# OVSR.net
KiCad netlist of a schematic drawn in Altium Designer
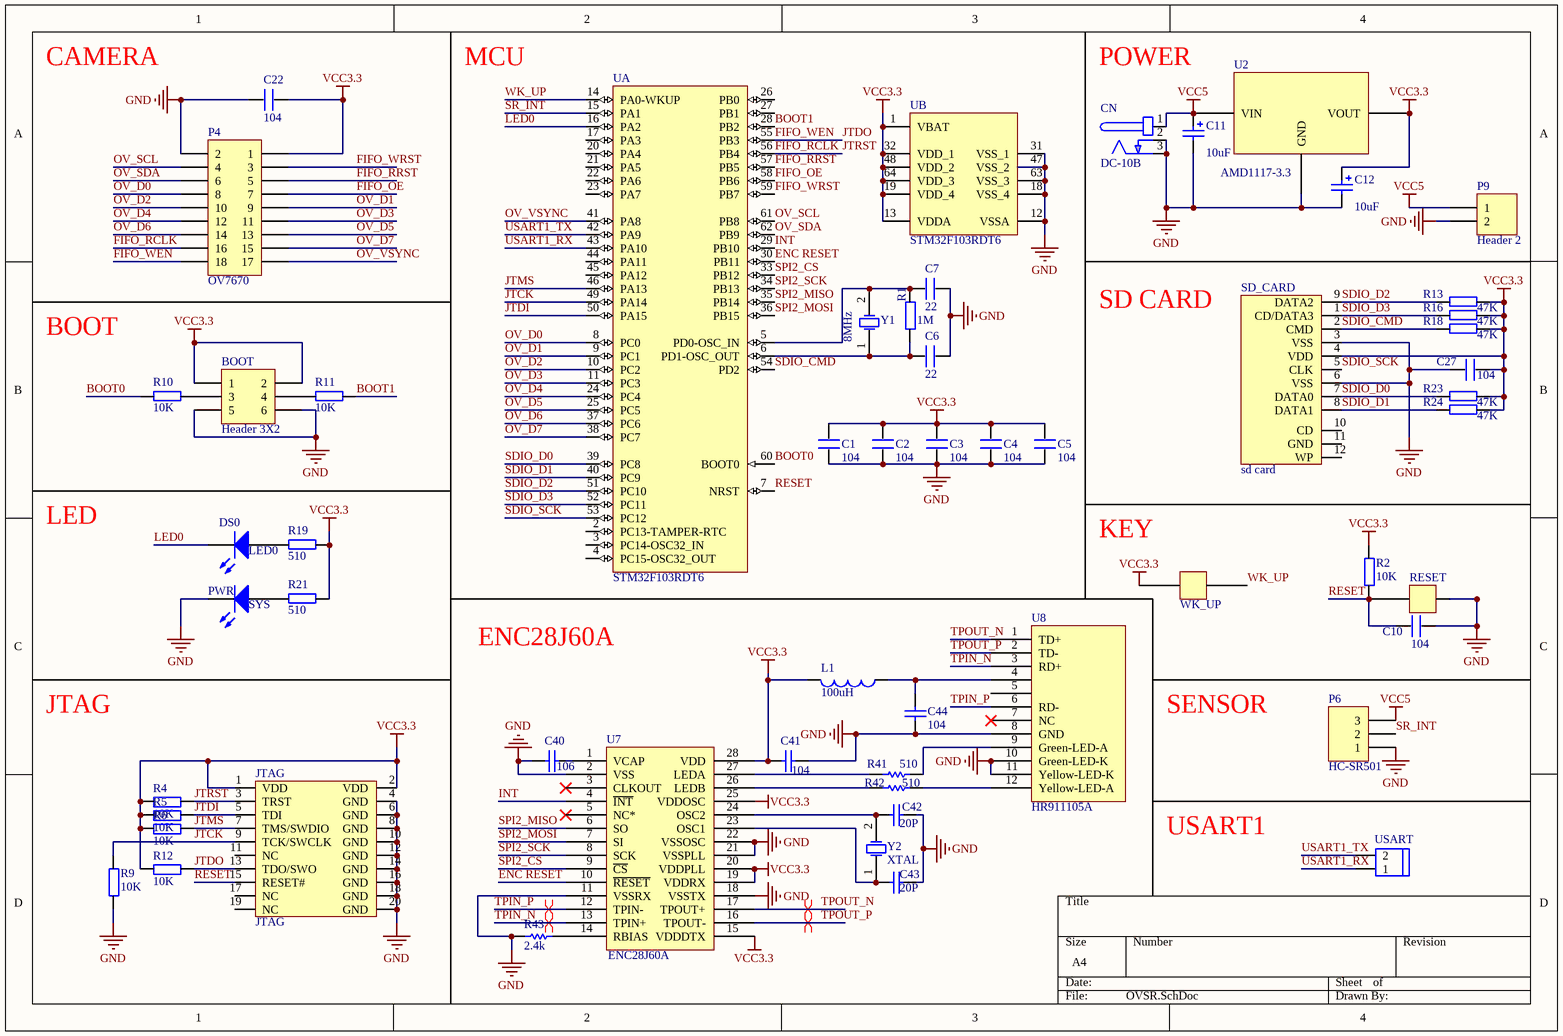
[diagram p0: OVSR.SchDoc]

(export (version "E")
  (design (tool "Eeschema 10.0.6"))
  (components
    (comp (ref "BOOT")
      (value "Header 3X2")
      (footprint "HDR2X3")
      (description "Header, 3-Pin, Dual row")
      (fields (field (name "PUBLISHER") "Altium Limited"))
      (libsource (lib "EliteSTM32封装库") (part "Header 3X2"))
    )
    (comp (ref "C1") (value "104") (footprint "CC1608-0603") (libsource (lib "EliteSTM32封装库") (part "C")))
    (comp (ref "C2") (value "104") (footprint "CC1608-0603") (libsource (lib "EliteSTM32封装库") (part "C")))
    (comp (ref "C3") (value "104") (footprint "CC1608-0603") (libsource (lib "EliteSTM32封装库") (part "C")))
    (comp (ref "C4") (value "104") (footprint "CC1608-0603") (libsource (lib "EliteSTM32封装库") (part "C")))
    (comp (ref "C5") (value "104") (footprint "CC1608-0603") (libsource (lib "EliteSTM32封装库") (part "C")))
    (comp (ref "C6") (value "22") (footprint "CC1608-0603") (libsource (lib "EliteSTM32封装库") (part "C_1")))
    (comp (ref "C7") (value "22") (footprint "CC1608-0603") (libsource (lib "EliteSTM32封装库") (part "C_1")))
    (comp (ref "C10") (value "104") (footprint "CC1608-0603") (libsource (lib "EliteSTM32封装库") (part "C")))
    (comp (ref "C11")
      (value "10uF")
      (footprint "CC1608-0603")
      (description "Polarized Capacitor (Axial)")
      (fields (field (name "Comment") "Cap Pol2") (field (name "PUBLISHER") "Altium Limited"))
      (libsource (lib "Miscellaneous Devices") (part "Cap Pol2"))
    )
    (comp (ref "C12")
      (value "10uF")
      (footprint "CC1608-0603")
      (description "Polarized Capacitor (Axial)")
      (fields (field (name "Comment") "Cap Pol2") (field (name "PUBLISHER") "Altium Limited"))
      (libsource (lib "Miscellaneous Devices") (part "Cap Pol2"))
    )
    (comp (ref "C22") (value "104") (footprint "CC1608-0603") (libsource (lib "EliteSTM32封装库") (part "C")))
    (comp (ref "C27") (value "104") (footprint "CC1608-0603") (libsource (lib "EliteSTM32封装库") (part "C")))
    (comp (ref "C40")
      (value "106")
      (footprint "Cr1608-0603")
      (description "Capacitor")
      (fields (field (name "Comment") "Cap") (field (name "PUBLISHER") "Altium Limited"))
      (libsource (lib "Miscellaneous Devices") (part "Cap"))
    )
    (comp (ref "C41")
      (value "104")
      (footprint "Cr1608-0603")
      (description "Capacitor")
      (fields (field (name "Comment") "Cap") (field (name "PUBLISHER") "Altium Limited"))
      (libsource (lib "Miscellaneous Devices") (part "Cap"))
    )
    (comp (ref "C42")
      (value "20P")
      (footprint "Cr1608-0603")
      (description "Capacitor")
      (fields (field (name "Comment") "Cap") (field (name "PUBLISHER") "Altium Limited"))
      (libsource (lib "Miscellaneous Devices") (part "Cap"))
    )
    (comp (ref "C43")
      (value "20P")
      (footprint "Cr1608-0603")
      (description "Capacitor")
      (fields (field (name "Comment") "Cap") (field (name "PUBLISHER") "Altium Limited"))
      (libsource (lib "Miscellaneous Devices") (part "Cap"))
    )
    (comp (ref "C44")
      (value "104")
      (footprint "Cr1608-0603")
      (description "Capacitor")
      (fields (field (name "Comment") "Cap") (field (name "PUBLISHER") "Altium Limited"))
      (libsource (lib "Miscellaneous Devices") (part "Cap"))
    )
    (comp (ref "CN")
      (value "DC-10B")
      (footprint "DC10B")
      (libsource (lib "STM32F207开发板（基本型）V1.0") (part "PJ202A"))
    )
    (comp (ref "DS0")
      (value "LED0")
      (footprint "WSN3:Cr2012-0805")
      (description "Typical RED, GREEN, YELLOW, AMBER GaAs LED")
      (fields (field (name "PUBLISHER") "Altium Limited"))
      (libsource (lib "EliteSTM32封装库") (part "LED2"))
    )
    (comp (ref "JTAG") (value "JTAG") (footprint "JTAG_20") (libsource (lib "EliteSTM32封装库") (part "JTAG")))
    (comp (ref "L1")
      (value "100uH")
      (footprint "1206")
      (description "Inductor")
      (fields (field (name "PUBLISHER") "Altium Limited"))
      (libsource (lib "Miscellaneous Devices") (part "Inductor"))
    )
    (comp (ref "P4")
      (value "OV7670")
      (footprint "HDR2X9")
      (description "Header, 9-Pin, Dual row")
      (fields (field (name "PUBLISHER") "Altium Limited"))
      (libsource (lib "EliteSTM32封装库") (part "Header 9X2"))
    )
    (comp (ref "P6")
      (value "HC-SR501")
      (footprint "5.08-3")
      (description "Header, 3-Pin")
      (fields (field (name "PUBLISHER") "Altium Limited"))
      (libsource (lib "WSN") (part "Header 3"))
    )
    (comp (ref "P9")
      (value "Header 2")
      (footprint "5.08-2")
      (description "Header, 2-Pin")
      (fields (field (name "PUBLISHER") "Altium Limited"))
      (libsource (lib "WSN") (part "Header 2"))
    )
    (comp (ref "PWR")
      (value "SYS")
      (footprint "WSN3:Cr2012-0805")
      (description "Typical RED, GREEN, YELLOW, AMBER GaAs LED")
      (fields (field (name "PUBLISHER") "Altium Limited"))
      (libsource (lib "EliteSTM32封装库") (part "LED2"))
    )
    (comp (ref "R1") (value "1M") (footprint "CR1608-0603") (libsource (lib "EliteSTM32封装库") (part "R")))
    (comp (ref "R2") (value "10K") (footprint "CR1608-0603") (libsource (lib "EliteSTM32封装库") (part "R")))
    (comp (ref "R4") (value "10K") (footprint "CR1608-0603") (libsource (lib "EliteSTM32封装库") (part "R")))
    (comp (ref "R5") (value "10K") (footprint "CR1608-0603") (libsource (lib "EliteSTM32封装库") (part "R")))
    (comp (ref "R6") (value "10K") (footprint "CR1608-0603") (libsource (lib "EliteSTM32封装库") (part "R")))
    (comp (ref "R9") (value "10K") (footprint "CR1608-0603") (libsource (lib "EliteSTM32封装库") (part "R")))
    (comp (ref "R10") (value "10K") (footprint "CR1608-0603") (libsource (lib "EliteSTM32封装库") (part "R")))
    (comp (ref "R11") (value "10K") (footprint "CR1608-0603") (libsource (lib "EliteSTM32封装库") (part "R")))
    (comp (ref "R12") (value "10K") (footprint "CR1608-0603") (libsource (lib "EliteSTM32封装库") (part "R")))
    (comp (ref "R13") (value "47K") (footprint "CR1608-0603") (libsource (lib "EliteSTM32封装库") (part "R")))
    (comp (ref "R16") (value "47K") (footprint "CR1608-0603") (libsource (lib "EliteSTM32封装库") (part "R")))
    (comp (ref "R18") (value "47K") (footprint "CR1608-0603") (libsource (lib "EliteSTM32封装库") (part "R")))
    (comp (ref "R19") (value "510") (footprint "CR1608-0603") (libsource (lib "EliteSTM32封装库") (part "R")))
    (comp (ref "R21") (value "510") (footprint "CR1608-0603") (libsource (lib "EliteSTM32封装库") (part "R")))
    (comp (ref "R23") (value "47K") (footprint "CR1608-0603") (libsource (lib "EliteSTM32封装库") (part "R")))
    (comp (ref "R24") (value "47K") (footprint "CR1608-0603") (libsource (lib "EliteSTM32封装库") (part "R")))
    (comp (ref "R41")
      (value "510")
      (footprint "Cr1608-0603")
      (description "Resistor")
      (fields (field (name "Comment") "Res1") (field (name "PUBLISHER") "Altium Limited"))
      (libsource (lib "Miscellaneous Devices") (part "Res1"))
    )
    (comp (ref "R42")
      (value "510")
      (footprint "Cr1608-0603")
      (description "Resistor")
      (fields (field (name "Comment") "Res1") (field (name "PUBLISHER") "Altium Limited"))
      (libsource (lib "Miscellaneous Devices") (part "Res1"))
    )
    (comp (ref "R43")
      (value "2.4k")
      (footprint "Cr1608-0603")
      (description "Resistor")
      (fields (field (name "Comment") "Res1") (field (name "PUBLISHER") "Altium Limited"))
      (libsource (lib "Miscellaneous Devices") (part "Res1"))
    )
    (comp (ref "RESET") (value "SW") (footprint "RST_SW") (libsource (lib "MCU") (part "SW")))
    (comp (ref "SD_CARD")
      (value "sd card")
      (footprint "SDCARD_L")
      (libsource (lib "EliteSTM32封装库") (part "sd card"))
    )
    (comp (ref "U")
      (value "STM32F103RDT6")
      (footprint "STM-LQFP64_N")
      (libsource (lib "STMicroelectronics STM32 F1") (part "STM32F103RDT6"))
    )
    (comp (ref "U2")
      (value "AMD1117-3.3")
      (footprint "SOT230P700X180-4N")
      (description "AMD1117-3.3芯片")
      (libsource (lib "MCU") (part "AMS1117-3.3"))
    )
    (comp (ref "U7")
      (value "ENC28J60A")
      (footprint "SSOP28_53MM_065P")
      (libsource (lib "mz") (part "ENC28J60A"))
    )
    (comp (ref "U8")
      (value "HR911105A")
      (footprint "STM32F207开发板（基本型）V1.0:HR911105A")
      (libsource (lib "mz") (part "HR911105A"))
    )
    (comp (ref "USART")
      (value "RS485")
      (footprint "HEAD2L-0.8")
      (libsource (lib "EliteSTM32封装库") (part "HEAD2"))
    )
    (comp (ref "WK_UP") (value "SW") (footprint "RST_SW") (libsource (lib "MCU") (part "SW")))
    (comp (ref "Y1")
      (value "8MHz")
      (footprint "WSN3:OSC1")
      (description "Crystal Oscillator")
      (fields (field (name "PUBLISHER") "Altium Limited"))
      (libsource (lib "EliteSTM32封装库") (part "XTAL"))
    )
    (comp (ref "Y2")
      (value "XTAL")
      (footprint "XTAL_US")
      (description "Crystal Oscillator")
      (fields (field (name "PUBLISHER") "Altium Limited"))
      (libsource (lib "Miscellaneous Devices") (part "XTAL"))
    )
  )
  (nets
    (net (code "1") (name "/BOOT0") (class "Default")
      (node (ref "R10") (pin "2") (pintype "passive"))
      (node (ref "U") (pin "60") (pinfunction "BOOT0_60") (pintype "input"))
    )
    (net (code "2") (name "/BOOT1") (class "Default")
      (node (ref "R11") (pin "1") (pintype "passive"))
      (node (ref "U") (pin "28") (pinfunction "PB2_28") (pintype "bidirectional"))
    )
    (net (code "3") (name "/ENC RESET") (class "Default")
      (node (ref "U") (pin "30") (pinfunction "PB11_30") (pintype "bidirectional"))
      (node (ref "U7") (pin "10") (pinfunction "~{RESET}_10") (pintype "passive"))
    )
    (net (code "4") (name "/FIFO_OE") (class "Default")
      (node (ref "P4") (pin "7") (pinfunction "7_7") (pintype "passive"))
      (node (ref "U") (pin "58") (pinfunction "PB6_58") (pintype "bidirectional"))
    )
    (net (code "5") (name "/FIFO_RCLK") (class "Default")
      (node (ref "JTAG") (pin "3") (pinfunction "TRST_3") (pintype "passive"))
      (node (ref "P4") (pin "16") (pinfunction "16_16") (pintype "passive"))
      (node (ref "R4") (pin "2") (pintype "passive"))
      (node (ref "U") (pin "56") (pinfunction "PB4_56") (pintype "bidirectional"))
    )
    (net (code "6") (name "/FIFO_RRST") (class "Default")
      (node (ref "P4") (pin "5") (pinfunction "5_5") (pintype "passive"))
      (node (ref "U") (pin "57") (pinfunction "PB5_57") (pintype "bidirectional"))
    )
    (net (code "7") (name "/FIFO_WEN") (class "Default")
      (node (ref "JTAG") (pin "13") (pinfunction "TDO/SWO_13") (pintype "passive"))
      (node (ref "P4") (pin "18") (pinfunction "18_18") (pintype "passive"))
      (node (ref "R12") (pin "2") (pintype "passive"))
      (node (ref "U") (pin "55") (pinfunction "PB3_55") (pintype "bidirectional"))
    )
    (net (code "8") (name "/FIFO_WRST") (class "Default")
      (node (ref "P4") (pin "3") (pinfunction "3_3") (pintype "passive"))
      (node (ref "U") (pin "59") (pinfunction "PB7_59") (pintype "bidirectional"))
    )
    (net (code "9") (name "/INT") (class "Default")
      (node (ref "U") (pin "29") (pinfunction "PB10_29") (pintype "bidirectional"))
      (node (ref "U7") (pin "4") (pinfunction "~{INT}_4") (pintype "passive"))
    )
    (net (code "10") (name "/JTCK") (class "Default")
      (node (ref "JTAG") (pin "9") (pinfunction "TCK/SWCLK_9") (pintype "passive"))
      (node (ref "R9") (pin "2") (pintype "passive"))
      (node (ref "U") (pin "49") (pinfunction "PA14_49") (pintype "bidirectional"))
    )
    (net (code "11") (name "/JTDI") (class "Default")
      (node (ref "JTAG") (pin "5") (pinfunction "TDI_5") (pintype "passive"))
      (node (ref "R5") (pin "2") (pintype "passive"))
      (node (ref "U") (pin "50") (pinfunction "PA15_50") (pintype "bidirectional"))
    )
    (net (code "12") (name "/JTMS") (class "Default")
      (node (ref "JTAG") (pin "7") (pinfunction "TMS/SWDIO_7") (pintype "passive"))
      (node (ref "R6") (pin "2") (pintype "passive"))
      (node (ref "U") (pin "46") (pinfunction "PA13_46") (pintype "bidirectional"))
    )
    (net (code "13") (name "/LED0") (class "Default")
      (node (ref "DS0") (pin "2") (pinfunction "K_2") (pintype "passive"))
      (node (ref "U") (pin "16") (pinfunction "PA2_16") (pintype "bidirectional"))
    )
    (net (code "14") (name "/OV_D0") (class "Default")
      (node (ref "P4") (pin "8") (pinfunction "8_8") (pintype "passive"))
      (node (ref "U") (pin "8") (pinfunction "PC0_8") (pintype "bidirectional"))
    )
    (net (code "15") (name "/OV_D1") (class "Default")
      (node (ref "P4") (pin "9") (pinfunction "9_9") (pintype "passive"))
      (node (ref "U") (pin "9") (pinfunction "PC1_9") (pintype "bidirectional"))
    )
    (net (code "16") (name "/OV_D2") (class "Default")
      (node (ref "P4") (pin "10") (pinfunction "10_10") (pintype "passive"))
      (node (ref "U") (pin "10") (pinfunction "PC2_10") (pintype "bidirectional"))
    )
    (net (code "17") (name "/OV_D3") (class "Default")
      (node (ref "P4") (pin "11") (pinfunction "11_11") (pintype "passive"))
      (node (ref "U") (pin "11") (pinfunction "PC3_11") (pintype "bidirectional"))
    )
    (net (code "18") (name "/OV_D4") (class "Default")
      (node (ref "P4") (pin "12") (pinfunction "12_12") (pintype "passive"))
      (node (ref "U") (pin "24") (pinfunction "PC4_24") (pintype "bidirectional"))
    )
    (net (code "19") (name "/OV_D5") (class "Default")
      (node (ref "P4") (pin "13") (pinfunction "13_13") (pintype "passive"))
      (node (ref "U") (pin "25") (pinfunction "PC5_25") (pintype "bidirectional"))
    )
    (net (code "20") (name "/OV_D6") (class "Default")
      (node (ref "P4") (pin "14") (pinfunction "14_14") (pintype "passive"))
      (node (ref "U") (pin "37") (pinfunction "PC6_37") (pintype "bidirectional"))
    )
    (net (code "21") (name "/OV_D7") (class "Default")
      (node (ref "P4") (pin "15") (pinfunction "15_15") (pintype "passive"))
      (node (ref "U") (pin "38") (pinfunction "PC7_38") (pintype "bidirectional"))
    )
    (net (code "22") (name "/OV_SCL") (class "Default")
      (node (ref "P4") (pin "4") (pinfunction "4_4") (pintype "passive"))
      (node (ref "U") (pin "61") (pinfunction "PB8_61") (pintype "bidirectional"))
    )
    (net (code "23") (name "/OV_SDA") (class "Default")
      (node (ref "P4") (pin "6") (pinfunction "6_6") (pintype "passive"))
      (node (ref "U") (pin "62") (pinfunction "PB9_62") (pintype "bidirectional"))
    )
    (net (code "24") (name "/OV_VSYNC") (class "Default")
      (node (ref "P4") (pin "17") (pinfunction "17_17") (pintype "passive"))
      (node (ref "U") (pin "41") (pinfunction "PA8_41") (pintype "bidirectional"))
    )
    (net (code "25") (name "/RESET") (class "Default")
      (node (ref "C10") (pin "2") (pintype "passive"))
      (node (ref "JTAG") (pin "15") (pinfunction "RESET#_15") (pintype "passive"))
      (node (ref "R2") (pin "1") (pintype "passive"))
      (node (ref "RESET") (pin "1") (pinfunction "1_1") (pintype "passive"))
      (node (ref "U") (pin "7") (pinfunction "NRST_7") (pintype "bidirectional"))
    )
    (net (code "26") (name "/SDIO_CMD") (class "Default")
      (node (ref "R18") (pin "2") (pintype "passive"))
      (node (ref "SD_CARD") (pin "2") (pinfunction "CMD_2") (pintype "passive"))
      (node (ref "U") (pin "54") (pinfunction "PD2_54") (pintype "bidirectional"))
    )
    (net (code "27") (name "/SDIO_D0") (class "Default")
      (node (ref "R23") (pin "2") (pintype "passive"))
      (node (ref "SD_CARD") (pin "7") (pinfunction "DATA0_7") (pintype "passive"))
      (node (ref "U") (pin "39") (pinfunction "PC8_39") (pintype "bidirectional"))
    )
    (net (code "28") (name "/SDIO_D1") (class "Default")
      (node (ref "R24") (pin "2") (pintype "passive"))
      (node (ref "SD_CARD") (pin "8") (pinfunction "DATA1_8") (pintype "passive"))
      (node (ref "U") (pin "40") (pinfunction "PC9_40") (pintype "bidirectional"))
    )
    (net (code "29") (name "/SDIO_D2") (class "Default")
      (node (ref "R13") (pin "2") (pintype "passive"))
      (node (ref "SD_CARD") (pin "9") (pinfunction "DATA2_9") (pintype "passive"))
      (node (ref "U") (pin "51") (pinfunction "PC10_51") (pintype "bidirectional"))
    )
    (net (code "30") (name "/SDIO_D3") (class "Default")
      (node (ref "R16") (pin "2") (pintype "passive"))
      (node (ref "SD_CARD") (pin "1") (pinfunction "CD/DATA3_1") (pintype "passive"))
      (node (ref "U") (pin "52") (pinfunction "PC11_52") (pintype "bidirectional"))
    )
    (net (code "31") (name "/SDIO_SCK") (class "Default")
      (node (ref "SD_CARD") (pin "5") (pinfunction "CLK_5") (pintype "passive"))
      (node (ref "U") (pin "53") (pinfunction "PC12_53") (pintype "bidirectional"))
    )
    (net (code "32") (name "/SPI2_CS") (class "Default")
      (node (ref "U") (pin "33") (pinfunction "PB12_33") (pintype "bidirectional"))
      (node (ref "U7") (pin "9") (pinfunction "~{CS}_9") (pintype "passive"))
    )
    (net (code "33") (name "/SPI2_MISO") (class "Default")
      (node (ref "U") (pin "35") (pinfunction "PB14_35") (pintype "bidirectional"))
      (node (ref "U7") (pin "6") (pinfunction "SO_6") (pintype "passive"))
    )
    (net (code "34") (name "/SPI2_MOSI") (class "Default")
      (node (ref "U") (pin "36") (pinfunction "PB15_36") (pintype "bidirectional"))
      (node (ref "U7") (pin "7") (pinfunction "SI_7") (pintype "passive"))
    )
    (net (code "35") (name "/SPI2_SCK") (class "Default")
      (node (ref "U") (pin "34") (pinfunction "PB13_34") (pintype "bidirectional"))
      (node (ref "U7") (pin "8") (pinfunction "SCK_8") (pintype "passive"))
    )
    (net (code "36") (name "/SR_INT") (class "Default")
      (node (ref "P6") (pin "2") (pinfunction "2_2") (pintype "passive"))
      (node (ref "U") (pin "15") (pinfunction "PA1_15") (pintype "bidirectional"))
    )
    (net (code "37") (name "/TPIN_N") (class "Default")
      (node (ref "U7") (pin "13") (pinfunction "TPIN+_13") (pintype "passive"))
      (node (ref "U8") (pin "3") (pinfunction "RD+_3") (pintype "passive"))
    )
    (net (code "38") (name "/TPIN_P") (class "Default")
      (node (ref "U7") (pin "12") (pinfunction "TPIN-_12") (pintype "passive"))
      (node (ref "U8") (pin "6") (pinfunction "RD-_6") (pintype "passive"))
    )
    (net (code "39") (name "/TPOUT_N") (class "Default")
      (node (ref "U7") (pin "17") (pinfunction "TPOUT+_17") (pintype "passive"))
      (node (ref "U8") (pin "1") (pinfunction "TD+_1") (pintype "passive"))
    )
    (net (code "40") (name "/TPOUT_P") (class "Default")
      (node (ref "U7") (pin "16") (pinfunction "TPOUT-_16") (pintype "passive"))
      (node (ref "U8") (pin "2") (pinfunction "TD-_2") (pintype "passive"))
    )
    (net (code "41") (name "/USART1_RX") (class "Default")
      (node (ref "U") (pin "43") (pinfunction "PA10_43") (pintype "bidirectional"))
      (node (ref "USART") (pin "1") (pinfunction "1_1") (pintype "passive"))
    )
    (net (code "42") (name "/USART1_TX") (class "Default")
      (node (ref "U") (pin "42") (pinfunction "PA9_42") (pintype "bidirectional"))
      (node (ref "USART") (pin "2") (pinfunction "2_2") (pintype "passive"))
    )
    (net (code "43") (name "/WK_UP") (class "Default")
      (node (ref "U") (pin "14") (pinfunction "PA0-WKUP_14") (pintype "bidirectional"))
      (node (ref "WK_UP") (pin "2") (pinfunction "2_2") (pintype "passive"))
    )
    (net (code "44") (name "GND") (class "Default")
      (node (ref "BOOT") (pin "5") (pinfunction "5_5") (pintype "passive"))
      (node (ref "BOOT") (pin "6") (pinfunction "6_6") (pintype "passive"))
      (node (ref "C1") (pin "1") (pintype "passive"))
      (node (ref "C10") (pin "1") (pintype "passive"))
      (node (ref "C11") (pin "2") (pinfunction "2_2") (pintype "passive"))
      (node (ref "C12") (pin "2") (pinfunction "2_2") (pintype "passive"))
      (node (ref "C2") (pin "1") (pintype "passive"))
      (node (ref "C22") (pin "2") (pintype "passive"))
      (node (ref "C27") (pin "2") (pintype "passive"))
      (node (ref "C3") (pin "1") (pintype "passive"))
      (node (ref "C4") (pin "1") (pintype "passive"))
      (node (ref "C40") (pin "1") (pinfunction "1_1") (pintype "passive"))
      (node (ref "C41") (pin "2") (pinfunction "2_2") (pintype "passive"))
      (node (ref "C42") (pin "2") (pinfunction "2_2") (pintype "passive"))
      (node (ref "C43") (pin "2") (pinfunction "2_2") (pintype "passive"))
      (node (ref "C44") (pin "2") (pinfunction "2_2") (pintype "passive"))
      (node (ref "C5") (pin "1") (pintype "passive"))
      (node (ref "C6") (pin "1") (pintype "passive"))
      (node (ref "C7") (pin "1") (pintype "passive"))
      (node (ref "CN") (pin "2") (pinfunction "GND_2") (pintype "passive"))
      (node (ref "CN") (pin "3") (pinfunction "GND_3") (pintype "passive"))
      (node (ref "JTAG") (pin "10") (pinfunction "GND_10") (pintype "passive"))
      (node (ref "JTAG") (pin "12") (pinfunction "GND_12") (pintype "passive"))
      (node (ref "JTAG") (pin "14") (pinfunction "GND_14") (pintype "passive"))
      (node (ref "JTAG") (pin "16") (pinfunction "GND_16") (pintype "passive"))
      (node (ref "JTAG") (pin "18") (pinfunction "GND_18") (pintype "passive"))
      (node (ref "JTAG") (pin "20") (pinfunction "GND_20") (pintype "passive"))
      (node (ref "JTAG") (pin "4") (pinfunction "GND_4") (pintype "passive"))
      (node (ref "JTAG") (pin "6") (pinfunction "GND_6") (pintype "passive"))
      (node (ref "JTAG") (pin "8") (pinfunction "GND_8") (pintype "passive"))
      (node (ref "P4") (pin "2") (pinfunction "2_2") (pintype "passive"))
      (node (ref "P6") (pin "1") (pinfunction "1_1") (pintype "passive"))
      (node (ref "P9") (pin "2") (pinfunction "2_2") (pintype "passive"))
      (node (ref "PWR") (pin "2") (pinfunction "K_2") (pintype "passive"))
      (node (ref "R43") (pin "2") (pinfunction "2_2") (pintype "passive"))
      (node (ref "R9") (pin "1") (pintype "passive"))
      (node (ref "RESET") (pin "2") (pinfunction "2_2") (pintype "passive"))
      (node (ref "SD_CARD") (pin "3") (pinfunction "VSS_3") (pintype "passive"))
      (node (ref "SD_CARD") (pin "6") (pinfunction "VSS_6") (pintype "passive"))
      (node (ref "U") (pin "12") (pinfunction "VSSA_12") (pintype "power_in"))
      (node (ref "U") (pin "18") (pinfunction "VSS_4_18") (pintype "power_in"))
      (node (ref "U") (pin "31") (pinfunction "VSS_1_31") (pintype "power_in"))
      (node (ref "U") (pin "47") (pinfunction "VSS_2_47") (pintype "power_in"))
      (node (ref "U") (pin "63") (pinfunction "VSS_3_63") (pintype "power_in"))
      (node (ref "U2") (pin "1") (pinfunction "GND_1") (pintype "passive"))
      (node (ref "U7") (pin "11") (pinfunction "VSSRX_11") (pintype "passive"))
      (node (ref "U7") (pin "18") (pinfunction "VSSTX_18") (pintype "passive"))
      (node (ref "U7") (pin "2") (pinfunction "VSS_2") (pintype "passive"))
      (node (ref "U7") (pin "21") (pinfunction "VSSPLL_21") (pintype "passive"))
      (node (ref "U7") (pin "22") (pinfunction "VSSOSC_22") (pintype "passive"))
      (node (ref "U8") (pin "10") (pinfunction "Green-LED-K_10") (pintype "passive"))
      (node (ref "U8") (pin "11") (pinfunction "Yellow-LED-K_11") (pintype "passive"))
      (node (ref "U8") (pin "8") (pinfunction "GND_8") (pintype "passive"))
    )
    (net (code "45") (name "Net-(BOOT-Pad3)") (class "Default")
      (node (ref "BOOT") (pin "3") (pinfunction "3_3") (pintype "passive"))
      (node (ref "R10") (pin "1") (pintype "passive"))
    )
    (net (code "46") (name "Net-(BOOT-Pad4)") (class "Default")
      (node (ref "BOOT") (pin "4") (pinfunction "4_4") (pintype "passive"))
      (node (ref "R11") (pin "2") (pintype "passive"))
    )
    (net (code "47") (name "Net-(C44-Pad1)") (class "Default")
      (node (ref "C44") (pin "1") (pinfunction "1_1") (pintype "passive"))
      (node (ref "L1") (pin "1") (pinfunction "1_1") (pintype "passive"))
      (node (ref "U8") (pin "4") (pintype "passive"))
    )
    (net (code "48") (name "Net-(DS0-A)") (class "Default")
      (node (ref "DS0") (pin "1") (pinfunction "A_1") (pintype "passive"))
      (node (ref "R19") (pin "2") (pintype "passive"))
    )
    (net (code "49") (name "Net-(PWR-A)") (class "Default")
      (node (ref "PWR") (pin "1") (pinfunction "A_1") (pintype "passive"))
      (node (ref "R21") (pin "2") (pintype "passive"))
    )
    (net (code "50") (name "Net-(U7-LEDA)") (class "Default")
      (node (ref "R41") (pin "1") (pinfunction "1_1") (pintype "passive"))
      (node (ref "U7") (pin "27") (pinfunction "LEDA_27") (pintype "passive"))
    )
    (net (code "51") (name "Net-(U7-LEDB)") (class "Default")
      (node (ref "R42") (pin "1") (pinfunction "1_1") (pintype "passive"))
      (node (ref "U7") (pin "26") (pinfunction "LEDB_26") (pintype "passive"))
    )
    (net (code "52") (name "Net-(U7-OSC1)") (class "Default")
      (node (ref "C43") (pin "1") (pinfunction "1_1") (pintype "passive"))
      (node (ref "U7") (pin "23") (pinfunction "OSC1_23") (pintype "passive"))
      (node (ref "Y2") (pin "1") (pinfunction "OSC1_1") (pintype "passive"))
    )
    (net (code "53") (name "Net-(U7-OSC2)") (class "Default")
      (node (ref "C42") (pin "1") (pinfunction "1_1") (pintype "passive"))
      (node (ref "U7") (pin "24") (pinfunction "OSC2_24") (pintype "passive"))
      (node (ref "Y2") (pin "2") (pinfunction "OSC2_2") (pintype "passive"))
    )
    (net (code "54") (name "Net-(U7-RBIAS)") (class "Default")
      (node (ref "R43") (pin "1") (pinfunction "1_1") (pintype "passive"))
      (node (ref "U7") (pin "14") (pinfunction "RBIAS_14") (pintype "passive"))
    )
    (net (code "55") (name "Net-(U7-VCAP)") (class "Default")
      (node (ref "C40") (pin "2") (pinfunction "2_2") (pintype "passive"))
      (node (ref "U7") (pin "1") (pinfunction "VCAP_1") (pintype "passive"))
    )
    (net (code "56") (name "Net-(U8-Green-LED-A)") (class "Default")
      (node (ref "R41") (pin "2") (pinfunction "2_2") (pintype "passive"))
      (node (ref "U8") (pin "9") (pinfunction "Green-LED-A_9") (pintype "passive"))
    )
    (net (code "57") (name "Net-(U8-Yellow-LED-A)") (class "Default")
      (node (ref "R42") (pin "2") (pinfunction "2_2") (pintype "passive"))
      (node (ref "U8") (pin "12") (pinfunction "Yellow-LED-A_12") (pintype "passive"))
    )
    (net (code "58") (name "Net-(UA-PD0-OSC_IN)") (class "Default")
      (node (ref "C7") (pin "2") (pintype "passive"))
      (node (ref "R1") (pin "2") (pintype "passive"))
      (node (ref "U") (pin "5") (pinfunction "PD0-OSC_IN_5") (pintype "bidirectional"))
      (node (ref "Y1") (pin "2") (pinfunction "OSC2_2") (pintype "passive"))
    )
    (net (code "59") (name "Net-(UA-PD1-OSC_OUT)") (class "Default")
      (node (ref "C6") (pin "2") (pintype "passive"))
      (node (ref "R1") (pin "1") (pintype "passive"))
      (node (ref "U") (pin "6") (pinfunction "PD1-OSC_OUT_6") (pintype "bidirectional"))
      (node (ref "Y1") (pin "1") (pinfunction "OSC1_1") (pintype "passive"))
    )
    (net (code "60") (name "VCC3.3") (class "Default")
      (node (ref "BOOT") (pin "1") (pinfunction "1_1") (pintype "passive"))
      (node (ref "BOOT") (pin "2") (pinfunction "2_2") (pintype "passive"))
      (node (ref "C1") (pin "2") (pintype "passive"))
      (node (ref "C12") (pin "1") (pinfunction "1_1") (pintype "passive"))
      (node (ref "C2") (pin "2") (pintype "passive"))
      (node (ref "C22") (pin "1") (pintype "passive"))
      (node (ref "C27") (pin "1") (pintype "passive"))
      (node (ref "C3") (pin "2") (pintype "passive"))
      (node (ref "C4") (pin "2") (pintype "passive"))
      (node (ref "C41") (pin "1") (pinfunction "1_1") (pintype "passive"))
      (node (ref "C5") (pin "2") (pintype "passive"))
      (node (ref "JTAG") (pin "1") (pinfunction "VDD_1") (pintype "passive"))
      (node (ref "JTAG") (pin "2") (pinfunction "VDD_2") (pintype "passive"))
      (node (ref "L1") (pin "2") (pinfunction "2_2") (pintype "passive"))
      (node (ref "P4") (pin "1") (pinfunction "1_1") (pintype "passive"))
      (node (ref "R12") (pin "1") (pintype "passive"))
      (node (ref "R13") (pin "1") (pintype "passive"))
      (node (ref "R16") (pin "1") (pintype "passive"))
      (node (ref "R18") (pin "1") (pintype "passive"))
      (node (ref "R19") (pin "1") (pintype "passive"))
      (node (ref "R2") (pin "2") (pintype "passive"))
      (node (ref "R21") (pin "1") (pintype "passive"))
      (node (ref "R23") (pin "1") (pintype "passive"))
      (node (ref "R24") (pin "1") (pintype "passive"))
      (node (ref "R4") (pin "1") (pintype "passive"))
      (node (ref "R5") (pin "1") (pintype "passive"))
      (node (ref "R6") (pin "1") (pintype "passive"))
      (node (ref "SD_CARD") (pin "4") (pinfunction "VDD_4") (pintype "passive"))
      (node (ref "U") (pin "1") (pinfunction "VBAT_1") (pintype "power_in"))
      (node (ref "U") (pin "13") (pinfunction "VDDA_13") (pintype "power_in"))
      (node (ref "U") (pin "19") (pinfunction "VDD_4_19") (pintype "power_in"))
      (node (ref "U") (pin "32") (pinfunction "VDD_1_32") (pintype "power_in"))
      (node (ref "U") (pin "48") (pinfunction "VDD_2_48") (pintype "power_in"))
      (node (ref "U") (pin "64") (pinfunction "VDD_3_64") (pintype "power_in"))
      (node (ref "U2") (pin "2") (pinfunction "VOUT_2") (pintype "passive"))
      (node (ref "U7") (pin "15") (pinfunction "VDDDTX_15") (pintype "passive"))
      (node (ref "U7") (pin "19") (pinfunction "VDDRX_19") (pintype "passive"))
      (node (ref "U7") (pin "20") (pinfunction "VDDPLL_20") (pintype "passive"))
      (node (ref "U7") (pin "25") (pinfunction "VDDOSC_25") (pintype "passive"))
      (node (ref "U7") (pin "28") (pinfunction "VDD_28") (pintype "passive"))
      (node (ref "WK_UP") (pin "1") (pinfunction "1_1") (pintype "passive"))
    )
    (net (code "61") (name "VCC5") (class "Default")
      (node (ref "C11") (pin "1") (pinfunction "1_1") (pintype "passive"))
      (node (ref "CN") (pin "1") (pinfunction "+_1") (pintype "passive"))
      (node (ref "P6") (pin "3") (pinfunction "3_3") (pintype "passive"))
      (node (ref "P9") (pin "1") (pinfunction "1_1") (pintype "passive"))
      (node (ref "U2") (pin "3") (pinfunction "VIN_3") (pintype "passive"))
    )
    (net (code "62") (name "unconnected-(JTAG-NC-Pad11)") (class "Default")
      (node (ref "JTAG") (pin "11") (pinfunction "NC_11") (pintype "passive"))
    )
    (net (code "63") (name "unconnected-(JTAG-NC-Pad17)") (class "Default")
      (node (ref "JTAG") (pin "17") (pinfunction "NC_17") (pintype "passive"))
    )
    (net (code "64") (name "unconnected-(JTAG-NC-Pad19)") (class "Default")
      (node (ref "JTAG") (pin "19") (pinfunction "NC_19") (pintype "passive"))
    )
    (net (code "65") (name "unconnected-(SD_CARD-CD-Pad10)") (class "Default")
      (node (ref "SD_CARD") (pin "10") (pinfunction "CD_10") (pintype "passive"))
    )
    (net (code "66") (name "unconnected-(SD_CARD-GND-Pad11)") (class "Default")
      (node (ref "SD_CARD") (pin "11") (pinfunction "GND_11") (pintype "passive"))
    )
    (net (code "67") (name "unconnected-(SD_CARD-WP-Pad12)") (class "Default")
      (node (ref "SD_CARD") (pin "12") (pinfunction "WP_12") (pintype "passive"))
    )
    (net (code "68") (name "unconnected-(U7-CLKOUT-Pad3)") (class "Default")
      (node (ref "U7") (pin "3") (pinfunction "CLKOUT_3") (pintype "passive+no_connect"))
    )
    (net (code "69") (name "unconnected-(U7-NC*-Pad5)") (class "Default")
      (node (ref "U7") (pin "5") (pinfunction "NC*_5") (pintype "passive+no_connect"))
    )
    (net (code "70") (name "unconnected-(U8-NC-Pad7)") (class "Default")
      (node (ref "U8") (pin "7") (pinfunction "NC_7") (pintype "passive+no_connect"))
    )
    (net (code "71") (name "unconnected-(U8-Pad5)") (class "Default")
      (node (ref "U8") (pin "5") (pintype "passive"))
    )
    (net (code "72") (name "unconnected-(UA-PA3-Pad17)") (class "Default")
      (node (ref "U") (pin "17") (pinfunction "PA3_17") (pintype "bidirectional"))
    )
    (net (code "73") (name "unconnected-(UA-PA4-Pad20)") (class "Default")
      (node (ref "U") (pin "20") (pinfunction "PA4_20") (pintype "bidirectional"))
    )
    (net (code "74") (name "unconnected-(UA-PA5-Pad21)") (class "Default")
      (node (ref "U") (pin "21") (pinfunction "PA5_21") (pintype "bidirectional"))
    )
    (net (code "75") (name "unconnected-(UA-PA6-Pad22)") (class "Default")
      (node (ref "U") (pin "22") (pinfunction "PA6_22") (pintype "bidirectional"))
    )
    (net (code "76") (name "unconnected-(UA-PA7-Pad23)") (class "Default")
      (node (ref "U") (pin "23") (pinfunction "PA7_23") (pintype "bidirectional"))
    )
    (net (code "77") (name "unconnected-(UA-PA11-Pad44)") (class "Default")
      (node (ref "U") (pin "44") (pinfunction "PA11_44") (pintype "bidirectional"))
    )
    (net (code "78") (name "unconnected-(UA-PA12-Pad45)") (class "Default")
      (node (ref "U") (pin "45") (pinfunction "PA12_45") (pintype "bidirectional"))
    )
    (net (code "79") (name "unconnected-(UA-PB0-Pad26)") (class "Default")
      (node (ref "U") (pin "26") (pinfunction "PB0_26") (pintype "bidirectional"))
    )
    (net (code "80") (name "unconnected-(UA-PB1-Pad27)") (class "Default")
      (node (ref "U") (pin "27") (pinfunction "PB1_27") (pintype "bidirectional"))
    )
    (net (code "81") (name "unconnected-(UA-PC13-TAMPER-RTC-Pad2)") (class "Default")
      (node (ref "U") (pin "2") (pinfunction "PC13-TAMPER-RTC_2") (pintype "bidirectional"))
    )
    (net (code "82") (name "unconnected-(UA-PC14-OSC32_IN-Pad3)") (class "Default")
      (node (ref "U") (pin "3") (pinfunction "PC14-OSC32_IN_3") (pintype "bidirectional"))
    )
    (net (code "83") (name "unconnected-(UA-PC15-OSC32_OUT-Pad4)") (class "Default")
      (node (ref "U") (pin "4") (pinfunction "PC15-OSC32_OUT_4") (pintype "bidirectional"))
    )
  )
)
